# keypadv3.net
KiCad netlist of a schematic drawn in EAGLE
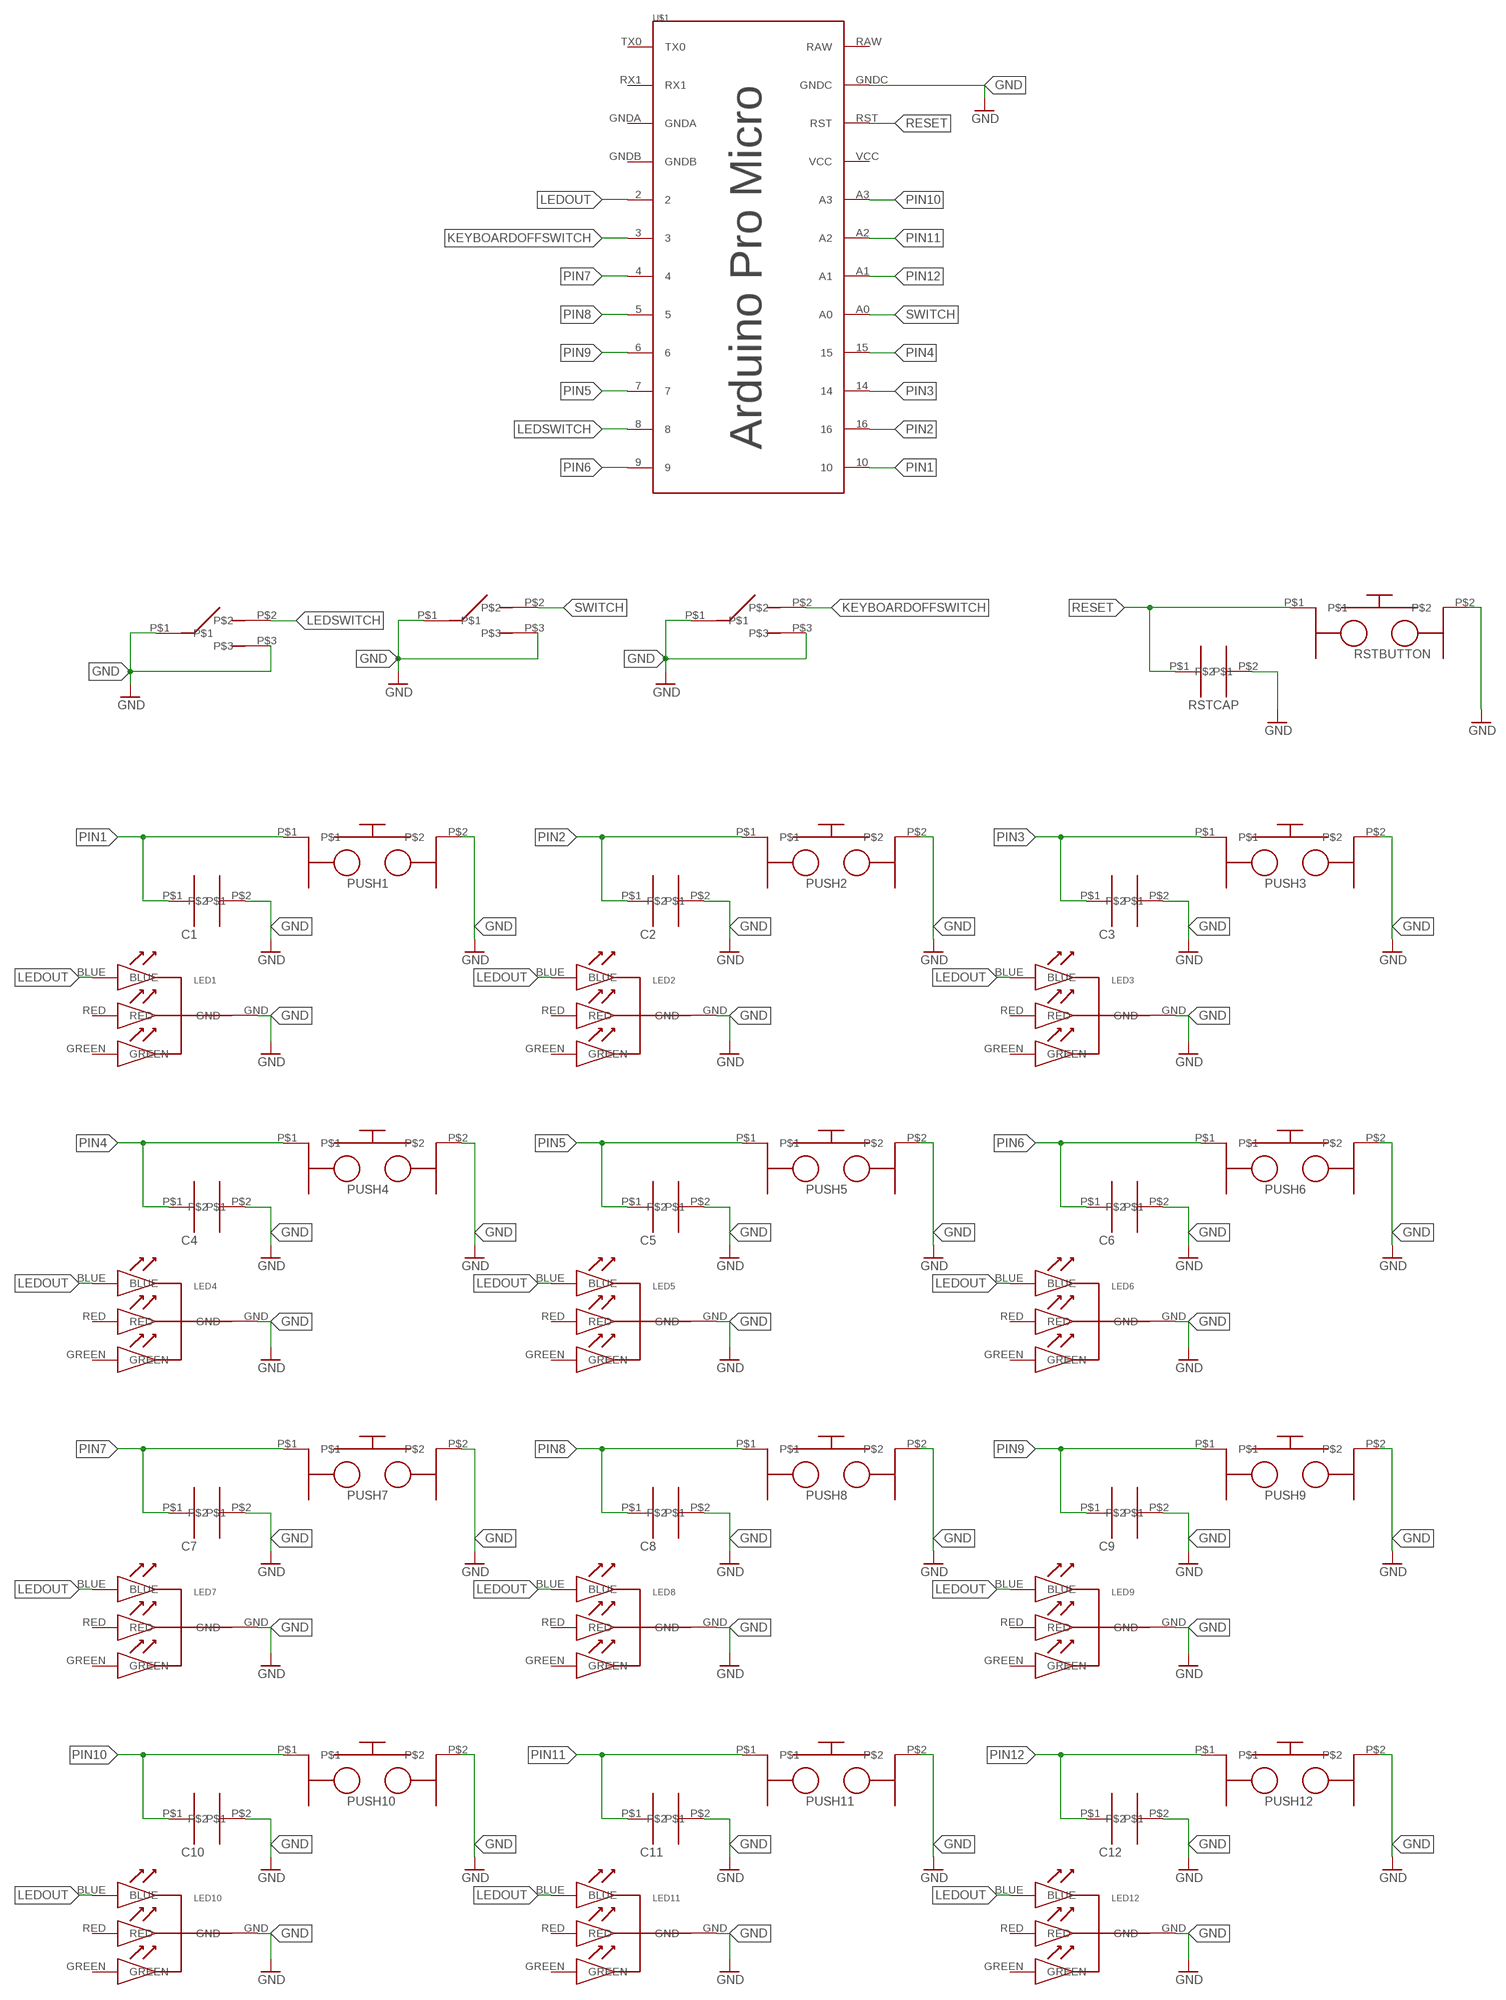
[diagram p0: schematic, sheet 1]

(export (version "E")
  (design (tool "Eeschema 10.0.6"))
  (components
    (comp (ref "C1")
      (value "CERAMICCAP")
      (footprint "eagle-import:CERAMICCAPACITOR")
      (libsource (lib "eagle-import") (part "CERAMICCAP"))
    )
    (comp (ref "C2")
      (value "CERAMICCAP")
      (footprint "eagle-import:CERAMICCAPACITOR")
      (libsource (lib "eagle-import") (part "CERAMICCAP"))
    )
    (comp (ref "C3")
      (value "CERAMICCAP")
      (footprint "eagle-import:CERAMICCAPACITOR")
      (libsource (lib "eagle-import") (part "CERAMICCAP"))
    )
    (comp (ref "C4")
      (value "CERAMICCAP")
      (footprint "eagle-import:CERAMICCAPACITOR")
      (libsource (lib "eagle-import") (part "CERAMICCAP"))
    )
    (comp (ref "C5")
      (value "CERAMICCAP")
      (footprint "eagle-import:CERAMICCAPACITOR")
      (libsource (lib "eagle-import") (part "CERAMICCAP"))
    )
    (comp (ref "C6")
      (value "CERAMICCAP")
      (footprint "eagle-import:CERAMICCAPACITOR")
      (libsource (lib "eagle-import") (part "CERAMICCAP"))
    )
    (comp (ref "C7")
      (value "CERAMICCAP")
      (footprint "eagle-import:CERAMICCAPACITOR")
      (libsource (lib "eagle-import") (part "CERAMICCAP"))
    )
    (comp (ref "C8")
      (value "CERAMICCAP")
      (footprint "eagle-import:CERAMICCAPACITOR")
      (libsource (lib "eagle-import") (part "CERAMICCAP"))
    )
    (comp (ref "C9")
      (value "CERAMICCAP")
      (footprint "eagle-import:CERAMICCAPACITOR")
      (libsource (lib "eagle-import") (part "CERAMICCAP"))
    )
    (comp (ref "C10")
      (value "CERAMICCAP")
      (footprint "eagle-import:CERAMICCAPACITOR")
      (libsource (lib "eagle-import") (part "CERAMICCAP"))
    )
    (comp (ref "C11")
      (value "CERAMICCAP")
      (footprint "eagle-import:CERAMICCAPACITOR")
      (libsource (lib "eagle-import") (part "CERAMICCAP"))
    )
    (comp (ref "C12")
      (value "CERAMICCAP")
      (footprint "eagle-import:CERAMICCAPACITOR")
      (libsource (lib "eagle-import") (part "CERAMICCAP"))
    )
    (comp (ref "LED1")
      (value "RGBLED5MMCOMMONCATHODE")
      (footprint "eagle-import:LEADSPREAD")
      (libsource (lib "eagle-import") (part "RGBLED5MMCOMMONCATHODE"))
    )
    (comp (ref "LED2")
      (value "RGBLED5MMCOMMONCATHODE")
      (footprint "eagle-import:LEADSPREAD")
      (libsource (lib "eagle-import") (part "RGBLED5MMCOMMONCATHODE"))
    )
    (comp (ref "LED3")
      (value "RGBLED5MMCOMMONCATHODE")
      (footprint "eagle-import:LEADSPREAD")
      (libsource (lib "eagle-import") (part "RGBLED5MMCOMMONCATHODE"))
    )
    (comp (ref "LED4")
      (value "RGBLED5MMCOMMONCATHODE")
      (footprint "eagle-import:LEADSPREAD")
      (libsource (lib "eagle-import") (part "RGBLED5MMCOMMONCATHODE"))
    )
    (comp (ref "LED5")
      (value "RGBLED5MMCOMMONCATHODE")
      (footprint "eagle-import:LEADSPREAD")
      (libsource (lib "eagle-import") (part "RGBLED5MMCOMMONCATHODE"))
    )
    (comp (ref "LED6")
      (value "RGBLED5MMCOMMONCATHODE")
      (footprint "eagle-import:LEADSPREAD")
      (libsource (lib "eagle-import") (part "RGBLED5MMCOMMONCATHODE"))
    )
    (comp (ref "LED7")
      (value "RGBLED5MMCOMMONCATHODE")
      (footprint "eagle-import:LEADSPREAD")
      (libsource (lib "eagle-import") (part "RGBLED5MMCOMMONCATHODE"))
    )
    (comp (ref "LED8")
      (value "RGBLED5MMCOMMONCATHODE")
      (footprint "eagle-import:LEADSPREAD")
      (libsource (lib "eagle-import") (part "RGBLED5MMCOMMONCATHODE"))
    )
    (comp (ref "LED9")
      (value "RGBLED5MMCOMMONCATHODE")
      (footprint "eagle-import:LEADSPREAD")
      (libsource (lib "eagle-import") (part "RGBLED5MMCOMMONCATHODE"))
    )
    (comp (ref "LED10")
      (value "RGBLED5MMCOMMONCATHODE")
      (footprint "eagle-import:LEADSPREAD")
      (libsource (lib "eagle-import") (part "RGBLED5MMCOMMONCATHODE"))
    )
    (comp (ref "LED11")
      (value "RGBLED5MMCOMMONCATHODE")
      (footprint "eagle-import:LEADSPREAD")
      (libsource (lib "eagle-import") (part "RGBLED5MMCOMMONCATHODE"))
    )
    (comp (ref "LED12")
      (value "RGBLED5MMCOMMONCATHODE")
      (footprint "eagle-import:LEADSPREAD")
      (libsource (lib "eagle-import") (part "RGBLED5MMCOMMONCATHODE"))
    )
    (comp (ref "PUSH1")
      (value "2LEADS")
      (footprint "eagle-import:2LEADS")
      (libsource (lib "eagle-import") (part "2LEADS"))
    )
    (comp (ref "PUSH2")
      (value "2LEADS")
      (footprint "eagle-import:2LEADS")
      (libsource (lib "eagle-import") (part "2LEADS"))
    )
    (comp (ref "PUSH3")
      (value "2LEADS")
      (footprint "eagle-import:2LEADS")
      (libsource (lib "eagle-import") (part "2LEADS"))
    )
    (comp (ref "PUSH4")
      (value "2LEADS")
      (footprint "eagle-import:2LEADS")
      (libsource (lib "eagle-import") (part "2LEADS"))
    )
    (comp (ref "PUSH5")
      (value "2LEADS")
      (footprint "eagle-import:2LEADS")
      (libsource (lib "eagle-import") (part "2LEADS"))
    )
    (comp (ref "PUSH6")
      (value "2LEADS")
      (footprint "eagle-import:2LEADS")
      (libsource (lib "eagle-import") (part "2LEADS"))
    )
    (comp (ref "PUSH7")
      (value "2LEADS")
      (footprint "eagle-import:2LEADS")
      (libsource (lib "eagle-import") (part "2LEADS"))
    )
    (comp (ref "PUSH8")
      (value "2LEADS")
      (footprint "eagle-import:2LEADS")
      (libsource (lib "eagle-import") (part "2LEADS"))
    )
    (comp (ref "PUSH9")
      (value "2LEADS")
      (footprint "eagle-import:2LEADS")
      (libsource (lib "eagle-import") (part "2LEADS"))
    )
    (comp (ref "PUSH10")
      (value "2LEADS")
      (footprint "eagle-import:2LEADS")
      (libsource (lib "eagle-import") (part "2LEADS"))
    )
    (comp (ref "PUSH11")
      (value "2LEADS")
      (footprint "eagle-import:2LEADS")
      (libsource (lib "eagle-import") (part "2LEADS"))
    )
    (comp (ref "PUSH12")
      (value "2LEADS")
      (footprint "eagle-import:2LEADS")
      (libsource (lib "eagle-import") (part "2LEADS"))
    )
    (comp (ref "RSTBUTTON")
      (value "2LEADS")
      (footprint "eagle-import:2LEADS")
      (libsource (lib "eagle-import") (part "2LEADS"))
    )
    (comp (ref "RSTCAP")
      (value "CERAMICCAP")
      (footprint "eagle-import:CERAMICCAPACITOR")
      (libsource (lib "eagle-import") (part "CERAMICCAP"))
    )
    (comp (ref "SWITCH1")
      (value "SWITCH")
      (footprint "eagle-import:THREEPINSWITCH")
      (libsource (lib "eagle-import") (part "SWITCH"))
    )
    (comp (ref "SWITCH2")
      (value "SWITCH")
      (footprint "eagle-import:THREEPINSWITCH")
      (libsource (lib "eagle-import") (part "SWITCH"))
    )
    (comp (ref "SWITCH3")
      (value "SWITCH")
      (footprint "eagle-import:THREEPINSWITCH")
      (libsource (lib "eagle-import") (part "SWITCH"))
    )
    (comp (ref "U$1")
      (value "ARDUINOPROMICRO")
      (footprint "eagle-import:ARDUINO_PRO_MICRO")
      (libsource (lib "eagle-import") (part "ARDUINOPROMICRO"))
    )
  )
  (nets
    (net (code "1") (name "GND") (class "Default")
      (node (ref "C1") (pin "P$2") (pinfunction "P$2_P$2") (pintype "bidirectional"))
      (node (ref "C10") (pin "P$2") (pinfunction "P$2_P$2") (pintype "bidirectional"))
      (node (ref "C11") (pin "P$2") (pinfunction "P$2_P$2") (pintype "bidirectional"))
      (node (ref "C12") (pin "P$2") (pinfunction "P$2_P$2") (pintype "bidirectional"))
      (node (ref "C2") (pin "P$2") (pinfunction "P$2_P$2") (pintype "bidirectional"))
      (node (ref "C3") (pin "P$2") (pinfunction "P$2_P$2") (pintype "bidirectional"))
      (node (ref "C4") (pin "P$2") (pinfunction "P$2_P$2") (pintype "bidirectional"))
      (node (ref "C5") (pin "P$2") (pinfunction "P$2_P$2") (pintype "bidirectional"))
      (node (ref "C6") (pin "P$2") (pinfunction "P$2_P$2") (pintype "bidirectional"))
      (node (ref "C7") (pin "P$2") (pinfunction "P$2_P$2") (pintype "bidirectional"))
      (node (ref "C8") (pin "P$2") (pinfunction "P$2_P$2") (pintype "bidirectional"))
      (node (ref "C9") (pin "P$2") (pinfunction "P$2_P$2") (pintype "bidirectional"))
      (node (ref "LED1") (pin "GND") (pinfunction "GND_GND") (pintype "bidirectional"))
      (node (ref "LED10") (pin "GND") (pinfunction "GND_GND") (pintype "bidirectional"))
      (node (ref "LED11") (pin "GND") (pinfunction "GND_GND") (pintype "bidirectional"))
      (node (ref "LED12") (pin "GND") (pinfunction "GND_GND") (pintype "bidirectional"))
      (node (ref "LED2") (pin "GND") (pinfunction "GND_GND") (pintype "bidirectional"))
      (node (ref "LED3") (pin "GND") (pinfunction "GND_GND") (pintype "bidirectional"))
      (node (ref "LED4") (pin "GND") (pinfunction "GND_GND") (pintype "bidirectional"))
      (node (ref "LED5") (pin "GND") (pinfunction "GND_GND") (pintype "bidirectional"))
      (node (ref "LED6") (pin "GND") (pinfunction "GND_GND") (pintype "bidirectional"))
      (node (ref "LED7") (pin "GND") (pinfunction "GND_GND") (pintype "bidirectional"))
      (node (ref "LED8") (pin "GND") (pinfunction "GND_GND") (pintype "bidirectional"))
      (node (ref "LED9") (pin "GND") (pinfunction "GND_GND") (pintype "bidirectional"))
      (node (ref "PUSH1") (pin "P$2") (pinfunction "P$2_P$2") (pintype "bidirectional"))
      (node (ref "PUSH10") (pin "P$2") (pinfunction "P$2_P$2") (pintype "bidirectional"))
      (node (ref "PUSH11") (pin "P$2") (pinfunction "P$2_P$2") (pintype "bidirectional"))
      (node (ref "PUSH12") (pin "P$2") (pinfunction "P$2_P$2") (pintype "bidirectional"))
      (node (ref "PUSH2") (pin "P$2") (pinfunction "P$2_P$2") (pintype "bidirectional"))
      (node (ref "PUSH3") (pin "P$2") (pinfunction "P$2_P$2") (pintype "bidirectional"))
      (node (ref "PUSH4") (pin "P$2") (pinfunction "P$2_P$2") (pintype "bidirectional"))
      (node (ref "PUSH5") (pin "P$2") (pinfunction "P$2_P$2") (pintype "bidirectional"))
      (node (ref "PUSH6") (pin "P$2") (pinfunction "P$2_P$2") (pintype "bidirectional"))
      (node (ref "PUSH7") (pin "P$2") (pinfunction "P$2_P$2") (pintype "bidirectional"))
      (node (ref "PUSH8") (pin "P$2") (pinfunction "P$2_P$2") (pintype "bidirectional"))
      (node (ref "PUSH9") (pin "P$2") (pinfunction "P$2_P$2") (pintype "bidirectional"))
      (node (ref "RSTBUTTON") (pin "P$2") (pinfunction "P$2_P$2") (pintype "bidirectional"))
      (node (ref "RSTCAP") (pin "P$2") (pinfunction "P$2_P$2") (pintype "bidirectional"))
      (node (ref "SWITCH1") (pin "P$1") (pinfunction "P$1_P$1") (pintype "bidirectional"))
      (node (ref "SWITCH1") (pin "P$3") (pinfunction "P$3_P$3") (pintype "bidirectional"))
      (node (ref "SWITCH2") (pin "P$1") (pinfunction "P$1_P$1") (pintype "bidirectional"))
      (node (ref "SWITCH2") (pin "P$3") (pinfunction "P$3_P$3") (pintype "bidirectional"))
      (node (ref "SWITCH3") (pin "P$1") (pinfunction "P$1_P$1") (pintype "bidirectional"))
      (node (ref "SWITCH3") (pin "P$3") (pinfunction "P$3_P$3") (pintype "bidirectional"))
      (node (ref "U$1") (pin "GNDC") (pinfunction "GNDC_GNDC") (pintype "bidirectional"))
    )
    (net (code "2") (name "KEYBOARDOFFSWITCH") (class "Default")
      (node (ref "SWITCH2") (pin "P$2") (pinfunction "P$2_P$2") (pintype "bidirectional"))
      (node (ref "U$1") (pin "3") (pinfunction "3_3") (pintype "bidirectional"))
    )
    (net (code "3") (name "LEDOUT") (class "Default")
      (node (ref "LED1") (pin "BLUE") (pinfunction "BLUE_BLUE") (pintype "bidirectional"))
      (node (ref "LED10") (pin "BLUE") (pinfunction "BLUE_BLUE") (pintype "bidirectional"))
      (node (ref "LED11") (pin "BLUE") (pinfunction "BLUE_BLUE") (pintype "bidirectional"))
      (node (ref "LED12") (pin "BLUE") (pinfunction "BLUE_BLUE") (pintype "bidirectional"))
      (node (ref "LED2") (pin "BLUE") (pinfunction "BLUE_BLUE") (pintype "bidirectional"))
      (node (ref "LED3") (pin "BLUE") (pinfunction "BLUE_BLUE") (pintype "bidirectional"))
      (node (ref "LED4") (pin "BLUE") (pinfunction "BLUE_BLUE") (pintype "bidirectional"))
      (node (ref "LED5") (pin "BLUE") (pinfunction "BLUE_BLUE") (pintype "bidirectional"))
      (node (ref "LED6") (pin "BLUE") (pinfunction "BLUE_BLUE") (pintype "bidirectional"))
      (node (ref "LED7") (pin "BLUE") (pinfunction "BLUE_BLUE") (pintype "bidirectional"))
      (node (ref "LED8") (pin "BLUE") (pinfunction "BLUE_BLUE") (pintype "bidirectional"))
      (node (ref "LED9") (pin "BLUE") (pinfunction "BLUE_BLUE") (pintype "bidirectional"))
      (node (ref "U$1") (pin "2") (pinfunction "2_2") (pintype "bidirectional"))
    )
    (net (code "4") (name "LEDSWITCH") (class "Default")
      (node (ref "SWITCH1") (pin "P$2") (pinfunction "P$2_P$2") (pintype "bidirectional"))
      (node (ref "U$1") (pin "8") (pinfunction "8_8") (pintype "bidirectional"))
    )
    (net (code "5") (name "PIN1") (class "Default")
      (node (ref "C1") (pin "P$1") (pinfunction "P$1_P$1") (pintype "bidirectional"))
      (node (ref "PUSH1") (pin "P$1") (pinfunction "P$1_P$1") (pintype "bidirectional"))
      (node (ref "U$1") (pin "10") (pinfunction "10_10") (pintype "bidirectional"))
    )
    (net (code "6") (name "PIN2") (class "Default")
      (node (ref "C2") (pin "P$1") (pinfunction "P$1_P$1") (pintype "bidirectional"))
      (node (ref "PUSH2") (pin "P$1") (pinfunction "P$1_P$1") (pintype "bidirectional"))
      (node (ref "U$1") (pin "16") (pinfunction "16_16") (pintype "bidirectional"))
    )
    (net (code "7") (name "PIN3") (class "Default")
      (node (ref "C3") (pin "P$1") (pinfunction "P$1_P$1") (pintype "bidirectional"))
      (node (ref "PUSH3") (pin "P$1") (pinfunction "P$1_P$1") (pintype "bidirectional"))
      (node (ref "U$1") (pin "14") (pinfunction "14_14") (pintype "bidirectional"))
    )
    (net (code "8") (name "PIN4") (class "Default")
      (node (ref "C4") (pin "P$1") (pinfunction "P$1_P$1") (pintype "bidirectional"))
      (node (ref "PUSH4") (pin "P$1") (pinfunction "P$1_P$1") (pintype "bidirectional"))
      (node (ref "U$1") (pin "15") (pinfunction "15_15") (pintype "bidirectional"))
    )
    (net (code "9") (name "PIN5") (class "Default")
      (node (ref "C5") (pin "P$1") (pinfunction "P$1_P$1") (pintype "bidirectional"))
      (node (ref "PUSH5") (pin "P$1") (pinfunction "P$1_P$1") (pintype "bidirectional"))
      (node (ref "U$1") (pin "7") (pinfunction "7_7") (pintype "bidirectional"))
    )
    (net (code "10") (name "PIN6") (class "Default")
      (node (ref "C6") (pin "P$1") (pinfunction "P$1_P$1") (pintype "bidirectional"))
      (node (ref "PUSH6") (pin "P$1") (pinfunction "P$1_P$1") (pintype "bidirectional"))
      (node (ref "U$1") (pin "9") (pinfunction "9_9") (pintype "bidirectional"))
    )
    (net (code "11") (name "PIN7") (class "Default")
      (node (ref "C7") (pin "P$1") (pinfunction "P$1_P$1") (pintype "bidirectional"))
      (node (ref "PUSH7") (pin "P$1") (pinfunction "P$1_P$1") (pintype "bidirectional"))
      (node (ref "U$1") (pin "4") (pinfunction "4_4") (pintype "bidirectional"))
    )
    (net (code "12") (name "PIN8") (class "Default")
      (node (ref "C8") (pin "P$1") (pinfunction "P$1_P$1") (pintype "bidirectional"))
      (node (ref "PUSH8") (pin "P$1") (pinfunction "P$1_P$1") (pintype "bidirectional"))
      (node (ref "U$1") (pin "5") (pinfunction "5_5") (pintype "bidirectional"))
    )
    (net (code "13") (name "PIN9") (class "Default")
      (node (ref "C9") (pin "P$1") (pinfunction "P$1_P$1") (pintype "bidirectional"))
      (node (ref "PUSH9") (pin "P$1") (pinfunction "P$1_P$1") (pintype "bidirectional"))
      (node (ref "U$1") (pin "6") (pinfunction "6_6") (pintype "bidirectional"))
    )
    (net (code "14") (name "PIN10") (class "Default")
      (node (ref "C10") (pin "P$1") (pinfunction "P$1_P$1") (pintype "bidirectional"))
      (node (ref "PUSH10") (pin "P$1") (pinfunction "P$1_P$1") (pintype "bidirectional"))
      (node (ref "U$1") (pin "A3") (pinfunction "A3_A3") (pintype "bidirectional"))
    )
    (net (code "15") (name "PIN11") (class "Default")
      (node (ref "C11") (pin "P$1") (pinfunction "P$1_P$1") (pintype "bidirectional"))
      (node (ref "PUSH11") (pin "P$1") (pinfunction "P$1_P$1") (pintype "bidirectional"))
      (node (ref "U$1") (pin "A2") (pinfunction "A2_A2") (pintype "bidirectional"))
    )
    (net (code "16") (name "PIN12") (class "Default")
      (node (ref "C12") (pin "P$1") (pinfunction "P$1_P$1") (pintype "bidirectional"))
      (node (ref "PUSH12") (pin "P$1") (pinfunction "P$1_P$1") (pintype "bidirectional"))
      (node (ref "U$1") (pin "A1") (pinfunction "A1_A1") (pintype "bidirectional"))
    )
    (net (code "17") (name "RESET") (class "Default")
      (node (ref "RSTBUTTON") (pin "P$1") (pinfunction "P$1_P$1") (pintype "bidirectional"))
      (node (ref "RSTCAP") (pin "P$1") (pinfunction "P$1_P$1") (pintype "bidirectional"))
      (node (ref "U$1") (pin "RST") (pinfunction "RST_RST") (pintype "bidirectional"))
    )
    (net (code "18") (name "SWITCH") (class "Default")
      (node (ref "SWITCH3") (pin "P$2") (pinfunction "P$2_P$2") (pintype "bidirectional"))
      (node (ref "U$1") (pin "A0") (pinfunction "A0_A0") (pintype "bidirectional"))
    )
    (net (code "19") (name "unconnected-(LED1-PadGREEN)") (class "Default")
      (node (ref "LED1") (pin "GREEN") (pinfunction "GREEN_GREEN") (pintype "bidirectional"))
    )
    (net (code "20") (name "unconnected-(LED1-PadRED)") (class "Default")
      (node (ref "LED1") (pin "RED") (pinfunction "RED_RED") (pintype "bidirectional"))
    )
    (net (code "21") (name "unconnected-(LED2-PadGREEN)") (class "Default")
      (node (ref "LED2") (pin "GREEN") (pinfunction "GREEN_GREEN") (pintype "bidirectional"))
    )
    (net (code "22") (name "unconnected-(LED2-PadRED)") (class "Default")
      (node (ref "LED2") (pin "RED") (pinfunction "RED_RED") (pintype "bidirectional"))
    )
    (net (code "23") (name "unconnected-(LED3-PadGREEN)") (class "Default")
      (node (ref "LED3") (pin "GREEN") (pinfunction "GREEN_GREEN") (pintype "bidirectional"))
    )
    (net (code "24") (name "unconnected-(LED3-PadRED)") (class "Default")
      (node (ref "LED3") (pin "RED") (pinfunction "RED_RED") (pintype "bidirectional"))
    )
    (net (code "25") (name "unconnected-(LED4-PadGREEN)") (class "Default")
      (node (ref "LED4") (pin "GREEN") (pinfunction "GREEN_GREEN") (pintype "bidirectional"))
    )
    (net (code "26") (name "unconnected-(LED4-PadRED)") (class "Default")
      (node (ref "LED4") (pin "RED") (pinfunction "RED_RED") (pintype "bidirectional"))
    )
    (net (code "27") (name "unconnected-(LED5-PadGREEN)") (class "Default")
      (node (ref "LED5") (pin "GREEN") (pinfunction "GREEN_GREEN") (pintype "bidirectional"))
    )
    (net (code "28") (name "unconnected-(LED5-PadRED)") (class "Default")
      (node (ref "LED5") (pin "RED") (pinfunction "RED_RED") (pintype "bidirectional"))
    )
    (net (code "29") (name "unconnected-(LED6-PadGREEN)") (class "Default")
      (node (ref "LED6") (pin "GREEN") (pinfunction "GREEN_GREEN") (pintype "bidirectional"))
    )
    (net (code "30") (name "unconnected-(LED6-PadRED)") (class "Default")
      (node (ref "LED6") (pin "RED") (pinfunction "RED_RED") (pintype "bidirectional"))
    )
    (net (code "31") (name "unconnected-(LED7-PadGREEN)") (class "Default")
      (node (ref "LED7") (pin "GREEN") (pinfunction "GREEN_GREEN") (pintype "bidirectional"))
    )
    (net (code "32") (name "unconnected-(LED7-PadRED)") (class "Default")
      (node (ref "LED7") (pin "RED") (pinfunction "RED_RED") (pintype "bidirectional"))
    )
    (net (code "33") (name "unconnected-(LED8-PadGREEN)") (class "Default")
      (node (ref "LED8") (pin "GREEN") (pinfunction "GREEN_GREEN") (pintype "bidirectional"))
    )
    (net (code "34") (name "unconnected-(LED8-PadRED)") (class "Default")
      (node (ref "LED8") (pin "RED") (pinfunction "RED_RED") (pintype "bidirectional"))
    )
    (net (code "35") (name "unconnected-(LED9-PadGREEN)") (class "Default")
      (node (ref "LED9") (pin "GREEN") (pinfunction "GREEN_GREEN") (pintype "bidirectional"))
    )
    (net (code "36") (name "unconnected-(LED9-PadRED)") (class "Default")
      (node (ref "LED9") (pin "RED") (pinfunction "RED_RED") (pintype "bidirectional"))
    )
    (net (code "37") (name "unconnected-(LED10-PadGREEN)") (class "Default")
      (node (ref "LED10") (pin "GREEN") (pinfunction "GREEN_GREEN") (pintype "bidirectional"))
    )
    (net (code "38") (name "unconnected-(LED10-PadRED)") (class "Default")
      (node (ref "LED10") (pin "RED") (pinfunction "RED_RED") (pintype "bidirectional"))
    )
    (net (code "39") (name "unconnected-(LED11-PadGREEN)") (class "Default")
      (node (ref "LED11") (pin "GREEN") (pinfunction "GREEN_GREEN") (pintype "bidirectional"))
    )
    (net (code "40") (name "unconnected-(LED11-PadRED)") (class "Default")
      (node (ref "LED11") (pin "RED") (pinfunction "RED_RED") (pintype "bidirectional"))
    )
    (net (code "41") (name "unconnected-(LED12-PadGREEN)") (class "Default")
      (node (ref "LED12") (pin "GREEN") (pinfunction "GREEN_GREEN") (pintype "bidirectional"))
    )
    (net (code "42") (name "unconnected-(LED12-PadRED)") (class "Default")
      (node (ref "LED12") (pin "RED") (pinfunction "RED_RED") (pintype "bidirectional"))
    )
    (net (code "43") (name "unconnected-(U$1-PadGNDA)") (class "Default")
      (node (ref "U$1") (pin "GNDA") (pinfunction "GNDA_GNDA") (pintype "bidirectional"))
    )
    (net (code "44") (name "unconnected-(U$1-PadGNDB)") (class "Default")
      (node (ref "U$1") (pin "GNDB") (pinfunction "GNDB_GNDB") (pintype "bidirectional"))
    )
    (net (code "45") (name "unconnected-(U$1-PadRAW)") (class "Default")
      (node (ref "U$1") (pin "RAW") (pinfunction "RAW_RAW") (pintype "bidirectional"))
    )
    (net (code "46") (name "unconnected-(U$1-PadRX1)") (class "Default")
      (node (ref "U$1") (pin "RX1") (pinfunction "RX1_RX1") (pintype "bidirectional"))
    )
    (net (code "47") (name "unconnected-(U$1-PadTX0)") (class "Default")
      (node (ref "U$1") (pin "TX0") (pinfunction "TX0_TX0") (pintype "bidirectional"))
    )
    (net (code "48") (name "unconnected-(U$1-PadVCC)") (class "Default")
      (node (ref "U$1") (pin "VCC") (pinfunction "VCC_VCC") (pintype "bidirectional"))
    )
  )
)
